# ak8975_spi.net
KiCad netlist of a schematic drawn in Altium Designer
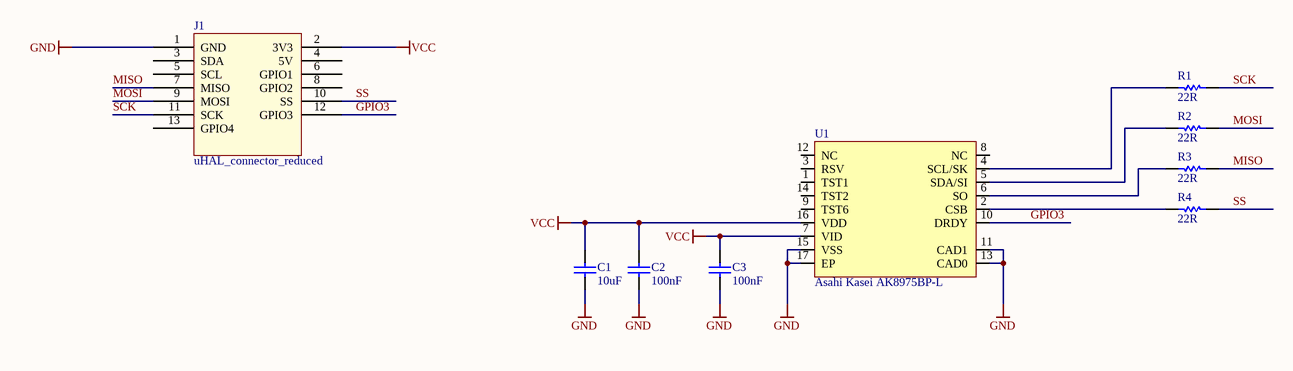
[diagram p0: ak8975_spi.SchDoc]

(export (version "E")
  (design (tool "Eeschema 10.0.6"))
  (components
    (comp (ref "C1")
      (value "Murata GCM188R71H104KA57D")
      (footprint "CAPC1608X90X35ML10T15")
      (description "CAP CER 0.1UF 50V 10% X7R 0603")
      (fields (field (name "CAPACITANCE") "10uF"))
      (libsource (lib "CommunityVault") (part "CMP-119667-3"))
    )
    (comp (ref "C2")
      (value "Murata GCM188R71H104KA57D")
      (footprint "CAPC1608X90X35ML10T15")
      (description "CAP CER 0.1UF 50V 10% X7R 0603")
      (fields (field (name "CAPACITANCE") "100nF"))
      (libsource (lib "CommunityVault") (part "CMP-119667-3"))
    )
    (comp (ref "C3")
      (value "Murata GCM188R71H104KA57D")
      (footprint "CAPC1608X90X35ML10T15")
      (description "CAP CER 0.1UF 50V 10% X7R 0603")
      (fields (field (name "CAPACITANCE") "100nF"))
      (libsource (lib "CommunityVault") (part "CMP-119667-3"))
    )
    (comp (ref "J1")
      (value "uHAL_connector_reduced")
      (footprint "PCB-45ncoppm4oopozvqifsq-1")
      (description "connector for uHAL with reduced pin number")
      (libsource (lib "CommunityVault") (part "CMP-2q23h2cwhjlfm8s6r7i8-1"))
    )
    (comp (ref "R1")
      (value "22R")
      (footprint "RESC1608X05N")
      (description "RCA Series 0603 0.1 W 0 O Jumper Surface Mount Thick Film Chip Resistor")
      (fields (field (name "MANUFACTURER PART NUMBER") "RCA06030000ZSEA"))
      (libsource (lib "CommunityVault") (part "SYM-31acf99032f6ee6b-1"))
    )
    (comp (ref "R2")
      (value "22R")
      (footprint "RESC1608X05N")
      (description "RCA Series 0603 0.1 W 0 O Jumper Surface Mount Thick Film Chip Resistor")
      (fields (field (name "MANUFACTURER PART NUMBER") "RCA06030000ZSEA"))
      (libsource (lib "CommunityVault") (part "SYM-31acf99032f6ee6b-1"))
    )
    (comp (ref "R3")
      (value "22R")
      (footprint "RESC1608X05N")
      (description "RCA Series 0603 0.1 W 0 O Jumper Surface Mount Thick Film Chip Resistor")
      (fields (field (name "MANUFACTURER PART NUMBER") "RCA06030000ZSEA"))
      (libsource (lib "CommunityVault") (part "SYM-31acf99032f6ee6b-1"))
    )
    (comp (ref "R4")
      (value "22R")
      (footprint "RESC1608X05N")
      (description "RCA Series 0603 0.1 W 0 O Jumper Surface Mount Thick Film Chip Resistor")
      (fields (field (name "MANUFACTURER PART NUMBER") "RCA06030000ZSEA"))
      (libsource (lib "CommunityVault") (part "SYM-31acf99032f6ee6b-1"))
    )
    (comp (ref "U1")
      (value "Asahi Kasei AK8975BP-L")
      (footprint "PCB-e1nx98ugchmxbk2nqwbe-1")
      (description "3-axis Electronic Compass")
      (fields (field (name "MANUFACTURER PART NUMBER") "AK8975BP-L"))
      (libsource (lib "CommunityVault") (part "CMP-3b1ff0b150b6e4d8-1"))
    )
  )
  (nets
    (net (code "1") (name "/GPIO3") (class "Default")
      (node (ref "J1") (pin "12") (pinfunction "GPIO3_12") (pintype "passive"))
      (node (ref "U1") (pin "10") (pinfunction "DRDY_10") (pintype "power_in"))
    )
    (net (code "2") (name "/MISO") (class "Default")
      (node (ref "J1") (pin "7") (pinfunction "MISO_7") (pintype "passive"))
      (node (ref "R3") (pin "1") (pinfunction "1_1") (pintype "passive"))
    )
    (net (code "3") (name "/MOSI") (class "Default")
      (node (ref "J1") (pin "9") (pinfunction "MOSI_9") (pintype "passive"))
      (node (ref "R2") (pin "1") (pinfunction "1_1") (pintype "passive"))
    )
    (net (code "4") (name "/SCK") (class "Default")
      (node (ref "J1") (pin "11") (pinfunction "SCK_11") (pintype "passive"))
      (node (ref "R1") (pin "1") (pinfunction "1_1") (pintype "passive"))
    )
    (net (code "5") (name "/SS") (class "Default")
      (node (ref "J1") (pin "10") (pinfunction "SS_10") (pintype "passive"))
      (node (ref "R4") (pin "1") (pinfunction "1_1") (pintype "passive"))
    )
    (net (code "6") (name "GND") (class "Default")
      (node (ref "C1") (pin "2") (pinfunction "2_2") (pintype "passive"))
      (node (ref "C2") (pin "2") (pinfunction "2_2") (pintype "passive"))
      (node (ref "C3") (pin "2") (pinfunction "2_2") (pintype "passive"))
      (node (ref "J1") (pin "1") (pinfunction "GND_1") (pintype "passive"))
      (node (ref "U1") (pin "11") (pinfunction "CAD1_11") (pintype "power_in"))
      (node (ref "U1") (pin "13") (pinfunction "CAD0_13") (pintype "power_in"))
      (node (ref "U1") (pin "15") (pinfunction "VSS_15") (pintype "power_in"))
      (node (ref "U1") (pin "17") (pinfunction "EP_17") (pintype "power_in"))
    )
    (net (code "7") (name "Net-(U1-CSB)") (class "Default")
      (node (ref "R4") (pin "2") (pinfunction "2_2") (pintype "passive"))
      (node (ref "U1") (pin "2") (pinfunction "CSB_2") (pintype "power_in"))
    )
    (net (code "8") (name "Net-(U1-SCL{slash}SK)") (class "Default")
      (node (ref "R1") (pin "2") (pinfunction "2_2") (pintype "passive"))
      (node (ref "U1") (pin "4") (pinfunction "SCL/SK_4") (pintype "power_in"))
    )
    (net (code "9") (name "Net-(U1-SDA{slash}SI)") (class "Default")
      (node (ref "R2") (pin "2") (pinfunction "2_2") (pintype "passive"))
      (node (ref "U1") (pin "5") (pinfunction "SDA/SI_5") (pintype "power_in"))
    )
    (net (code "10") (name "Net-(U1-SO)") (class "Default")
      (node (ref "R3") (pin "2") (pinfunction "2_2") (pintype "passive"))
      (node (ref "U1") (pin "6") (pinfunction "SO_6") (pintype "power_in"))
    )
    (net (code "11") (name "VCC") (class "Default")
      (node (ref "C1") (pin "1") (pinfunction "1_1") (pintype "passive"))
      (node (ref "C2") (pin "1") (pinfunction "1_1") (pintype "passive"))
      (node (ref "C3") (pin "1") (pinfunction "1_1") (pintype "passive"))
      (node (ref "J1") (pin "2") (pinfunction "3V3_2") (pintype "passive"))
      (node (ref "U1") (pin "16") (pinfunction "VDD_16") (pintype "power_in"))
      (node (ref "U1") (pin "7") (pinfunction "VID_7") (pintype "power_in"))
    )
    (net (code "12") (name "unconnected-(J1-5V-Pad4)") (class "Default")
      (node (ref "J1") (pin "4") (pinfunction "5V_4") (pintype "passive"))
    )
    (net (code "13") (name "unconnected-(J1-GPIO1-Pad6)") (class "Default")
      (node (ref "J1") (pin "6") (pinfunction "GPIO1_6") (pintype "passive"))
    )
    (net (code "14") (name "unconnected-(J1-GPIO2-Pad8)") (class "Default")
      (node (ref "J1") (pin "8") (pinfunction "GPIO2_8") (pintype "passive"))
    )
    (net (code "15") (name "unconnected-(J1-GPIO4-Pad13)") (class "Default")
      (node (ref "J1") (pin "13") (pinfunction "GPIO4_13") (pintype "passive"))
    )
    (net (code "16") (name "unconnected-(J1-SCL-Pad5)") (class "Default")
      (node (ref "J1") (pin "5") (pinfunction "SCL_5") (pintype "passive"))
    )
    (net (code "17") (name "unconnected-(J1-SDA-Pad3)") (class "Default")
      (node (ref "J1") (pin "3") (pinfunction "SDA_3") (pintype "passive"))
    )
    (net (code "18") (name "unconnected-(U1-NC-Pad8)") (class "Default")
      (node (ref "U1") (pin "8") (pinfunction "NC_8") (pintype "power_in"))
    )
    (net (code "19") (name "unconnected-(U1-NC-Pad12)") (class "Default")
      (node (ref "U1") (pin "12") (pinfunction "NC_12") (pintype "power_in"))
    )
    (net (code "20") (name "unconnected-(U1-RSV-Pad3)") (class "Default")
      (node (ref "U1") (pin "3") (pinfunction "RSV_3") (pintype "power_in"))
    )
    (net (code "21") (name "unconnected-(U1-TST1-Pad1)") (class "Default")
      (node (ref "U1") (pin "1") (pinfunction "TST1_1") (pintype "power_in"))
    )
    (net (code "22") (name "unconnected-(U1-TST2-Pad14)") (class "Default")
      (node (ref "U1") (pin "14") (pinfunction "TST2_14") (pintype "power_in"))
    )
    (net (code "23") (name "unconnected-(U1-TST6-Pad9)") (class "Default")
      (node (ref "U1") (pin "9") (pinfunction "TST6_9") (pintype "power_in"))
    )
  )
)
